# PCB4.net
KiCad netlist of a schematic drawn in EAGLE
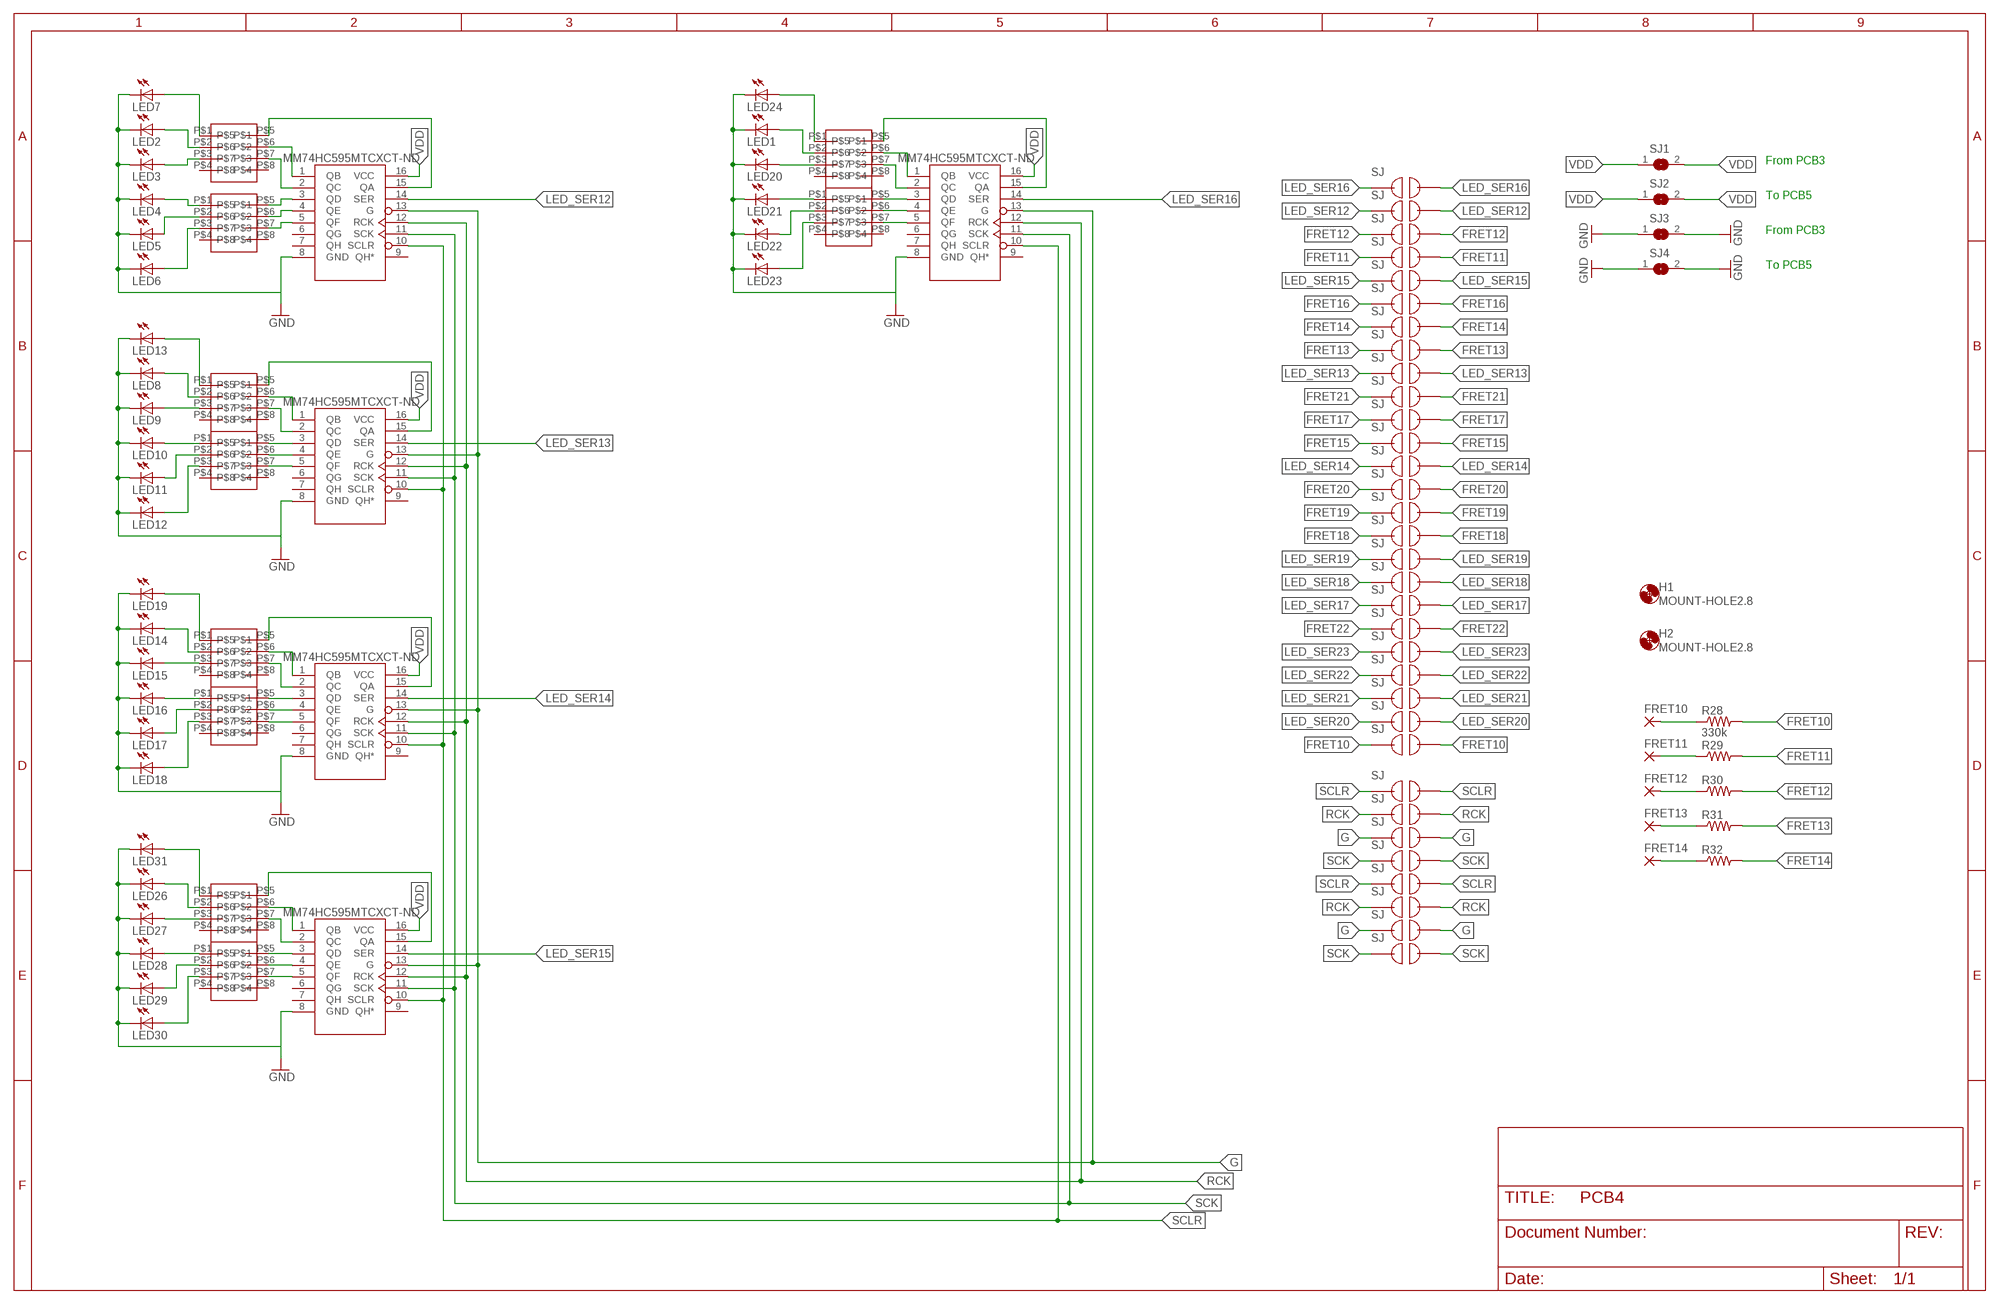
[diagram p0: schematic, sheet 1]

(export (version "E")
  (design (tool "Eeschema 10.0.6"))
  (components
    (comp (ref "FRET10")
      (value "2,54/0,9")
      (footprint "eagle-import:2,54_0,9")
      (libsource (lib "eagle-import") (part "2,54/0,9"))
    )
    (comp (ref "FRET11")
      (value "2,54/0,9")
      (footprint "eagle-import:2,54_0,9")
      (libsource (lib "eagle-import") (part "2,54/0,9"))
    )
    (comp (ref "FRET12")
      (value "2,54/0,9")
      (footprint "eagle-import:2,54_0,9")
      (libsource (lib "eagle-import") (part "2,54/0,9"))
    )
    (comp (ref "FRET13")
      (value "2,54/0,9")
      (footprint "eagle-import:2,54_0,9")
      (libsource (lib "eagle-import") (part "2,54/0,9"))
    )
    (comp (ref "FRET14")
      (value "2,54/0,9")
      (footprint "eagle-import:2,54_0,9")
      (libsource (lib "eagle-import") (part "2,54/0,9"))
    )
    (comp (ref "H1")
      (value "MOUNT-HOLE2.8")
      (footprint "eagle-import:2,8")
      (libsource (lib "eagle-import") (part "MOUNT-HOLE2.8"))
    )
    (comp (ref "H2")
      (value "MOUNT-HOLE2.8")
      (footprint "eagle-import:2,8")
      (libsource (lib "eagle-import") (part "MOUNT-HOLE2.8"))
    )
    (comp (ref "LED1")
      (value "LEDSMT1206")
      (footprint "eagle-import:1206")
      (libsource (lib "eagle-import") (part "LEDSMT1206"))
    )
    (comp (ref "LED2")
      (value "LEDSMT1206")
      (footprint "eagle-import:1206")
      (libsource (lib "eagle-import") (part "LEDSMT1206"))
    )
    (comp (ref "LED3")
      (value "LEDSMT1206")
      (footprint "eagle-import:1206")
      (libsource (lib "eagle-import") (part "LEDSMT1206"))
    )
    (comp (ref "LED4")
      (value "LEDSMT1206")
      (footprint "eagle-import:1206")
      (libsource (lib "eagle-import") (part "LEDSMT1206"))
    )
    (comp (ref "LED5")
      (value "LEDSMT1206")
      (footprint "eagle-import:1206")
      (libsource (lib "eagle-import") (part "LEDSMT1206"))
    )
    (comp (ref "LED6")
      (value "LEDSMT1206")
      (footprint "eagle-import:1206")
      (libsource (lib "eagle-import") (part "LEDSMT1206"))
    )
    (comp (ref "LED7")
      (value "LEDSMT1206")
      (footprint "eagle-import:1206")
      (libsource (lib "eagle-import") (part "LEDSMT1206"))
    )
    (comp (ref "LED8")
      (value "LEDSMT1206")
      (footprint "eagle-import:1206")
      (libsource (lib "eagle-import") (part "LEDSMT1206"))
    )
    (comp (ref "LED9")
      (value "LEDSMT1206")
      (footprint "eagle-import:1206")
      (libsource (lib "eagle-import") (part "LEDSMT1206"))
    )
    (comp (ref "LED10")
      (value "LEDSMT1206")
      (footprint "eagle-import:1206")
      (libsource (lib "eagle-import") (part "LEDSMT1206"))
    )
    (comp (ref "LED11")
      (value "LEDSMT1206")
      (footprint "eagle-import:1206")
      (libsource (lib "eagle-import") (part "LEDSMT1206"))
    )
    (comp (ref "LED12")
      (value "LEDSMT1206")
      (footprint "eagle-import:1206")
      (libsource (lib "eagle-import") (part "LEDSMT1206"))
    )
    (comp (ref "LED13")
      (value "LEDSMT1206")
      (footprint "eagle-import:1206")
      (libsource (lib "eagle-import") (part "LEDSMT1206"))
    )
    (comp (ref "LED14")
      (value "LEDSMT1206")
      (footprint "eagle-import:1206")
      (libsource (lib "eagle-import") (part "LEDSMT1206"))
    )
    (comp (ref "LED15")
      (value "LEDSMT1206")
      (footprint "eagle-import:1206")
      (libsource (lib "eagle-import") (part "LEDSMT1206"))
    )
    (comp (ref "LED16")
      (value "LEDSMT1206")
      (footprint "eagle-import:1206")
      (libsource (lib "eagle-import") (part "LEDSMT1206"))
    )
    (comp (ref "LED17")
      (value "LEDSMT1206")
      (footprint "eagle-import:1206")
      (libsource (lib "eagle-import") (part "LEDSMT1206"))
    )
    (comp (ref "LED18")
      (value "LEDSMT1206")
      (footprint "eagle-import:1206")
      (libsource (lib "eagle-import") (part "LEDSMT1206"))
    )
    (comp (ref "LED19")
      (value "LEDSMT1206")
      (footprint "eagle-import:1206")
      (libsource (lib "eagle-import") (part "LEDSMT1206"))
    )
    (comp (ref "LED20")
      (value "LEDSMT1206")
      (footprint "eagle-import:1206")
      (libsource (lib "eagle-import") (part "LEDSMT1206"))
    )
    (comp (ref "LED21")
      (value "LEDSMT1206")
      (footprint "eagle-import:1206")
      (libsource (lib "eagle-import") (part "LEDSMT1206"))
    )
    (comp (ref "LED22")
      (value "LEDSMT1206")
      (footprint "eagle-import:1206")
      (libsource (lib "eagle-import") (part "LEDSMT1206"))
    )
    (comp (ref "LED23")
      (value "LEDSMT1206")
      (footprint "eagle-import:1206")
      (libsource (lib "eagle-import") (part "LEDSMT1206"))
    )
    (comp (ref "LED24")
      (value "LEDSMT1206")
      (footprint "eagle-import:1206")
      (libsource (lib "eagle-import") (part "LEDSMT1206"))
    )
    (comp (ref "LED26")
      (value "LEDSMT1206")
      (footprint "eagle-import:1206")
      (libsource (lib "eagle-import") (part "LEDSMT1206"))
    )
    (comp (ref "LED27")
      (value "LEDSMT1206")
      (footprint "eagle-import:1206")
      (libsource (lib "eagle-import") (part "LEDSMT1206"))
    )
    (comp (ref "LED28")
      (value "LEDSMT1206")
      (footprint "eagle-import:1206")
      (libsource (lib "eagle-import") (part "LEDSMT1206"))
    )
    (comp (ref "LED29")
      (value "LEDSMT1206")
      (footprint "eagle-import:1206")
      (libsource (lib "eagle-import") (part "LEDSMT1206"))
    )
    (comp (ref "LED30")
      (value "LEDSMT1206")
      (footprint "eagle-import:1206")
      (libsource (lib "eagle-import") (part "LEDSMT1206"))
    )
    (comp (ref "LED31")
      (value "LEDSMT1206")
      (footprint "eagle-import:1206")
      (libsource (lib "eagle-import") (part "LEDSMT1206"))
    )
    (comp (ref "R28")
      (value "330k")
      (footprint "eagle-import:R0805")
      (libsource (lib "eagle-import") (part "R-US_R0805"))
    )
    (comp (ref "R29")
      (value "R-US_R0805")
      (footprint "eagle-import:R0805")
      (libsource (lib "eagle-import") (part "R-US_R0805"))
    )
    (comp (ref "R30")
      (value "R-US_R0805")
      (footprint "eagle-import:R0805")
      (libsource (lib "eagle-import") (part "R-US_R0805"))
    )
    (comp (ref "R31")
      (value "R-US_R0805")
      (footprint "eagle-import:R0805")
      (libsource (lib "eagle-import") (part "R-US_R0805"))
    )
    (comp (ref "R32")
      (value "R-US_R0805")
      (footprint "eagle-import:R0805")
      (libsource (lib "eagle-import") (part "R-US_R0805"))
    )
    (comp (ref "SJ1") (value "SJ") (footprint "eagle-import:SJ") (libsource (lib "eagle-import") (part "SJ")))
    (comp (ref "SJ2") (value "SJ") (footprint "eagle-import:SJ") (libsource (lib "eagle-import") (part "SJ")))
    (comp (ref "SJ3") (value "SJ") (footprint "eagle-import:SJ") (libsource (lib "eagle-import") (part "SJ")))
    (comp (ref "SJ4") (value "SJ") (footprint "eagle-import:SJ") (libsource (lib "eagle-import") (part "SJ")))
    (comp (ref "U$1")
      (value "MM74HC595TSSOP-LD16")
      (footprint "eagle-import:MM74HC595MTCXCT-ND")
      (libsource (lib "eagle-import") (part "MM74HC595TSSOP-LD16"))
    )
    (comp (ref "U$2")
      (value "MM74HC595TSSOP-LD16")
      (footprint "eagle-import:MM74HC595MTCXCT-ND")
      (libsource (lib "eagle-import") (part "MM74HC595TSSOP-LD16"))
    )
    (comp (ref "U$3")
      (value "MM74HC595TSSOP-LD16")
      (footprint "eagle-import:MM74HC595MTCXCT-ND")
      (libsource (lib "eagle-import") (part "MM74HC595TSSOP-LD16"))
    )
    (comp (ref "U$4")
      (value "MM74HC595TSSOP-LD16")
      (footprint "eagle-import:MM74HC595MTCXCT-ND")
      (libsource (lib "eagle-import") (part "MM74HC595TSSOP-LD16"))
    )
    (comp (ref "U$5")
      (value "MM74HC595TSSOP-LD16")
      (footprint "eagle-import:MM74HC595MTCXCT-ND")
      (libsource (lib "eagle-import") (part "MM74HC595TSSOP-LD16"))
    )
    (comp (ref "U$6")
      (value "MNR04MRAPJ680")
      (footprint "eagle-import:MNR04")
      (libsource (lib "eagle-import") (part "MNR04MRAPJ680"))
    )
    (comp (ref "U$7")
      (value "MNR04MRAPJ680")
      (footprint "eagle-import:MNR04")
      (libsource (lib "eagle-import") (part "MNR04MRAPJ680"))
    )
    (comp (ref "U$8")
      (value "MNR04MRAPJ680")
      (footprint "eagle-import:MNR04")
      (libsource (lib "eagle-import") (part "MNR04MRAPJ680"))
    )
    (comp (ref "U$9")
      (value "MNR04MRAPJ680")
      (footprint "eagle-import:MNR04")
      (libsource (lib "eagle-import") (part "MNR04MRAPJ680"))
    )
    (comp (ref "U$10")
      (value "MNR04MRAPJ680")
      (footprint "eagle-import:MNR04")
      (libsource (lib "eagle-import") (part "MNR04MRAPJ680"))
    )
    (comp (ref "U$11")
      (value "MNR04MRAPJ680")
      (footprint "eagle-import:MNR04")
      (libsource (lib "eagle-import") (part "MNR04MRAPJ680"))
    )
    (comp (ref "U$12")
      (value "MNR04MRAPJ680")
      (footprint "eagle-import:MNR04")
      (libsource (lib "eagle-import") (part "MNR04MRAPJ680"))
    )
    (comp (ref "U$13")
      (value "MNR04MRAPJ680")
      (footprint "eagle-import:MNR04")
      (libsource (lib "eagle-import") (part "MNR04MRAPJ680"))
    )
    (comp (ref "U$14")
      (value "MNR04MRAPJ680")
      (footprint "eagle-import:MNR04")
      (libsource (lib "eagle-import") (part "MNR04MRAPJ680"))
    )
    (comp (ref "U$15")
      (value "MNR04MRAPJ680")
      (footprint "eagle-import:MNR04")
      (libsource (lib "eagle-import") (part "MNR04MRAPJ680"))
    )
    (comp (ref "U$19")
      (value "JUMPER")
      (footprint "eagle-import:JUMPER")
      (libsource (lib "eagle-import") (part "JUMPER"))
    )
    (comp (ref "U$42")
      (value "JUMPER")
      (footprint "eagle-import:JUMPER")
      (libsource (lib "eagle-import") (part "JUMPER"))
    )
    (comp (ref "U$45")
      (value "JUMPER")
      (footprint "eagle-import:JUMPER")
      (libsource (lib "eagle-import") (part "JUMPER"))
    )
    (comp (ref "U$46")
      (value "JUMPER")
      (footprint "eagle-import:JUMPER")
      (libsource (lib "eagle-import") (part "JUMPER"))
    )
    (comp (ref "U$47")
      (value "JUMPER")
      (footprint "eagle-import:JUMPER")
      (libsource (lib "eagle-import") (part "JUMPER"))
    )
    (comp (ref "U$48")
      (value "JUMPER")
      (footprint "eagle-import:JUMPER")
      (libsource (lib "eagle-import") (part "JUMPER"))
    )
    (comp (ref "U$49")
      (value "JUMPER")
      (footprint "eagle-import:JUMPER")
      (libsource (lib "eagle-import") (part "JUMPER"))
    )
    (comp (ref "U$50")
      (value "JUMPER")
      (footprint "eagle-import:JUMPER")
      (libsource (lib "eagle-import") (part "JUMPER"))
    )
    (comp (ref "U$51")
      (value "JUMPER")
      (footprint "eagle-import:JUMPER")
      (libsource (lib "eagle-import") (part "JUMPER"))
    )
    (comp (ref "U$52")
      (value "JUMPER")
      (footprint "eagle-import:JUMPER")
      (libsource (lib "eagle-import") (part "JUMPER"))
    )
    (comp (ref "U$53")
      (value "JUMPER")
      (footprint "eagle-import:JUMPER")
      (libsource (lib "eagle-import") (part "JUMPER"))
    )
    (comp (ref "U$54")
      (value "JUMPER")
      (footprint "eagle-import:JUMPER")
      (libsource (lib "eagle-import") (part "JUMPER"))
    )
    (comp (ref "U$55")
      (value "JUMPER")
      (footprint "eagle-import:JUMPER")
      (libsource (lib "eagle-import") (part "JUMPER"))
    )
    (comp (ref "U$56")
      (value "JUMPER")
      (footprint "eagle-import:JUMPER")
      (libsource (lib "eagle-import") (part "JUMPER"))
    )
    (comp (ref "U$57")
      (value "JUMPER")
      (footprint "eagle-import:JUMPER")
      (libsource (lib "eagle-import") (part "JUMPER"))
    )
    (comp (ref "U$58")
      (value "JUMPER")
      (footprint "eagle-import:JUMPER")
      (libsource (lib "eagle-import") (part "JUMPER"))
    )
    (comp (ref "U$59")
      (value "JUMPER")
      (footprint "eagle-import:JUMPER")
      (libsource (lib "eagle-import") (part "JUMPER"))
    )
    (comp (ref "U$60")
      (value "JUMPER")
      (footprint "eagle-import:JUMPER")
      (libsource (lib "eagle-import") (part "JUMPER"))
    )
    (comp (ref "U$61")
      (value "JUMPER")
      (footprint "eagle-import:JUMPER")
      (libsource (lib "eagle-import") (part "JUMPER"))
    )
    (comp (ref "U$62")
      (value "JUMPER")
      (footprint "eagle-import:JUMPER")
      (libsource (lib "eagle-import") (part "JUMPER"))
    )
    (comp (ref "U$63")
      (value "JUMPER")
      (footprint "eagle-import:JUMPER")
      (libsource (lib "eagle-import") (part "JUMPER"))
    )
    (comp (ref "U$64")
      (value "JUMPER")
      (footprint "eagle-import:JUMPER")
      (libsource (lib "eagle-import") (part "JUMPER"))
    )
    (comp (ref "U$65")
      (value "JUMPER")
      (footprint "eagle-import:JUMPER")
      (libsource (lib "eagle-import") (part "JUMPER"))
    )
    (comp (ref "U$66")
      (value "JUMPER")
      (footprint "eagle-import:JUMPER")
      (libsource (lib "eagle-import") (part "JUMPER"))
    )
    (comp (ref "U$67")
      (value "JUMPER")
      (footprint "eagle-import:JUMPER")
      (libsource (lib "eagle-import") (part "JUMPER"))
    )
    (comp (ref "U$68")
      (value "JUMPER")
      (footprint "eagle-import:JUMPER")
      (libsource (lib "eagle-import") (part "JUMPER"))
    )
    (comp (ref "U$69")
      (value "JUMPER")
      (footprint "eagle-import:JUMPER")
      (libsource (lib "eagle-import") (part "JUMPER"))
    )
    (comp (ref "U$79")
      (value "JUMPER")
      (footprint "eagle-import:JUMPER")
      (libsource (lib "eagle-import") (part "JUMPER"))
    )
    (comp (ref "U$80")
      (value "JUMPER")
      (footprint "eagle-import:JUMPER")
      (libsource (lib "eagle-import") (part "JUMPER"))
    )
    (comp (ref "U$81")
      (value "JUMPER")
      (footprint "eagle-import:JUMPER")
      (libsource (lib "eagle-import") (part "JUMPER"))
    )
    (comp (ref "U$82")
      (value "JUMPER")
      (footprint "eagle-import:JUMPER")
      (libsource (lib "eagle-import") (part "JUMPER"))
    )
    (comp (ref "U$83")
      (value "JUMPER")
      (footprint "eagle-import:JUMPER")
      (libsource (lib "eagle-import") (part "JUMPER"))
    )
    (comp (ref "U$84")
      (value "JUMPER")
      (footprint "eagle-import:JUMPER")
      (libsource (lib "eagle-import") (part "JUMPER"))
    )
  )
  (nets
    (net (code "1") (name "FRET10") (class "Default")
      (node (ref "R28") (pin "2") (pinfunction "2_2") (pintype "passive"))
      (node (ref "U$69") (pin "P$1") (pinfunction "P$1_P$1") (pintype "bidirectional"))
      (node (ref "U$69") (pin "P$2") (pinfunction "P$2_P$2") (pintype "bidirectional"))
    )
    (net (code "2") (name "FRET11") (class "Default")
      (node (ref "R29") (pin "2") (pinfunction "2_2") (pintype "passive"))
      (node (ref "U$48") (pin "P$1") (pinfunction "P$1_P$1") (pintype "bidirectional"))
      (node (ref "U$48") (pin "P$2") (pinfunction "P$2_P$2") (pintype "bidirectional"))
    )
    (net (code "3") (name "FRET12") (class "Default")
      (node (ref "R30") (pin "2") (pinfunction "2_2") (pintype "passive"))
      (node (ref "U$47") (pin "P$1") (pinfunction "P$1_P$1") (pintype "bidirectional"))
      (node (ref "U$47") (pin "P$2") (pinfunction "P$2_P$2") (pintype "bidirectional"))
    )
    (net (code "4") (name "FRET13") (class "Default")
      (node (ref "R31") (pin "2") (pinfunction "2_2") (pintype "passive"))
      (node (ref "U$52") (pin "P$1") (pinfunction "P$1_P$1") (pintype "bidirectional"))
      (node (ref "U$52") (pin "P$2") (pinfunction "P$2_P$2") (pintype "bidirectional"))
    )
    (net (code "5") (name "FRET14") (class "Default")
      (node (ref "R32") (pin "2") (pinfunction "2_2") (pintype "passive"))
      (node (ref "U$51") (pin "P$1") (pinfunction "P$1_P$1") (pintype "bidirectional"))
      (node (ref "U$51") (pin "P$2") (pinfunction "P$2_P$2") (pintype "bidirectional"))
    )
    (net (code "6") (name "FRET15") (class "Default")
      (node (ref "U$56") (pin "P$1") (pinfunction "P$1_P$1") (pintype "bidirectional"))
      (node (ref "U$56") (pin "P$2") (pinfunction "P$2_P$2") (pintype "bidirectional"))
    )
    (net (code "7") (name "FRET16") (class "Default")
      (node (ref "U$50") (pin "P$1") (pinfunction "P$1_P$1") (pintype "bidirectional"))
      (node (ref "U$50") (pin "P$2") (pinfunction "P$2_P$2") (pintype "bidirectional"))
    )
    (net (code "8") (name "FRET17") (class "Default")
      (node (ref "U$55") (pin "P$1") (pinfunction "P$1_P$1") (pintype "bidirectional"))
      (node (ref "U$55") (pin "P$2") (pinfunction "P$2_P$2") (pintype "bidirectional"))
    )
    (net (code "9") (name "FRET18") (class "Default")
      (node (ref "U$60") (pin "P$1") (pinfunction "P$1_P$1") (pintype "bidirectional"))
      (node (ref "U$60") (pin "P$2") (pinfunction "P$2_P$2") (pintype "bidirectional"))
    )
    (net (code "10") (name "FRET19") (class "Default")
      (node (ref "U$59") (pin "P$1") (pinfunction "P$1_P$1") (pintype "bidirectional"))
      (node (ref "U$59") (pin "P$2") (pinfunction "P$2_P$2") (pintype "bidirectional"))
    )
    (net (code "11") (name "FRET20") (class "Default")
      (node (ref "U$58") (pin "P$1") (pinfunction "P$1_P$1") (pintype "bidirectional"))
      (node (ref "U$58") (pin "P$2") (pinfunction "P$2_P$2") (pintype "bidirectional"))
    )
    (net (code "12") (name "FRET21") (class "Default")
      (node (ref "U$54") (pin "P$1") (pinfunction "P$1_P$1") (pintype "bidirectional"))
      (node (ref "U$54") (pin "P$2") (pinfunction "P$2_P$2") (pintype "bidirectional"))
    )
    (net (code "13") (name "FRET22") (class "Default")
      (node (ref "U$64") (pin "P$1") (pinfunction "P$1_P$1") (pintype "bidirectional"))
      (node (ref "U$64") (pin "P$2") (pinfunction "P$2_P$2") (pintype "bidirectional"))
    )
    (net (code "14") (name "G") (class "Default")
      (node (ref "U$1") (pin "13") (pinfunction "G_13") (pintype "bidirectional"))
      (node (ref "U$2") (pin "13") (pinfunction "G_13") (pintype "bidirectional"))
      (node (ref "U$3") (pin "13") (pinfunction "G_13") (pintype "bidirectional"))
      (node (ref "U$4") (pin "13") (pinfunction "G_13") (pintype "bidirectional"))
      (node (ref "U$5") (pin "13") (pinfunction "G_13") (pintype "bidirectional"))
      (node (ref "U$80") (pin "P$1") (pinfunction "P$1_P$1") (pintype "bidirectional"))
      (node (ref "U$80") (pin "P$2") (pinfunction "P$2_P$2") (pintype "bidirectional"))
      (node (ref "U$84") (pin "P$1") (pinfunction "P$1_P$1") (pintype "bidirectional"))
      (node (ref "U$84") (pin "P$2") (pinfunction "P$2_P$2") (pintype "bidirectional"))
    )
    (net (code "15") (name "GND") (class "Default")
      (node (ref "LED1") (pin "C") (pinfunction "C_C") (pintype "passive"))
      (node (ref "LED10") (pin "C") (pinfunction "C_C") (pintype "passive"))
      (node (ref "LED11") (pin "C") (pinfunction "C_C") (pintype "passive"))
      (node (ref "LED12") (pin "C") (pinfunction "C_C") (pintype "passive"))
      (node (ref "LED13") (pin "C") (pinfunction "C_C") (pintype "passive"))
      (node (ref "LED14") (pin "C") (pinfunction "C_C") (pintype "passive"))
      (node (ref "LED15") (pin "C") (pinfunction "C_C") (pintype "passive"))
      (node (ref "LED16") (pin "C") (pinfunction "C_C") (pintype "passive"))
      (node (ref "LED17") (pin "C") (pinfunction "C_C") (pintype "passive"))
      (node (ref "LED18") (pin "C") (pinfunction "C_C") (pintype "passive"))
      (node (ref "LED19") (pin "C") (pinfunction "C_C") (pintype "passive"))
      (node (ref "LED2") (pin "C") (pinfunction "C_C") (pintype "passive"))
      (node (ref "LED20") (pin "C") (pinfunction "C_C") (pintype "passive"))
      (node (ref "LED21") (pin "C") (pinfunction "C_C") (pintype "passive"))
      (node (ref "LED22") (pin "C") (pinfunction "C_C") (pintype "passive"))
      (node (ref "LED23") (pin "C") (pinfunction "C_C") (pintype "passive"))
      (node (ref "LED24") (pin "C") (pinfunction "C_C") (pintype "passive"))
      (node (ref "LED26") (pin "C") (pinfunction "C_C") (pintype "passive"))
      (node (ref "LED27") (pin "C") (pinfunction "C_C") (pintype "passive"))
      (node (ref "LED28") (pin "C") (pinfunction "C_C") (pintype "passive"))
      (node (ref "LED29") (pin "C") (pinfunction "C_C") (pintype "passive"))
      (node (ref "LED3") (pin "C") (pinfunction "C_C") (pintype "passive"))
      (node (ref "LED30") (pin "C") (pinfunction "C_C") (pintype "passive"))
      (node (ref "LED31") (pin "C") (pinfunction "C_C") (pintype "passive"))
      (node (ref "LED4") (pin "C") (pinfunction "C_C") (pintype "passive"))
      (node (ref "LED5") (pin "C") (pinfunction "C_C") (pintype "passive"))
      (node (ref "LED6") (pin "C") (pinfunction "C_C") (pintype "passive"))
      (node (ref "LED7") (pin "C") (pinfunction "C_C") (pintype "passive"))
      (node (ref "LED8") (pin "C") (pinfunction "C_C") (pintype "passive"))
      (node (ref "LED9") (pin "C") (pinfunction "C_C") (pintype "passive"))
      (node (ref "SJ3") (pin "1") (pinfunction "1_1") (pintype "passive"))
      (node (ref "SJ3") (pin "2") (pinfunction "2_2") (pintype "passive"))
      (node (ref "SJ4") (pin "1") (pinfunction "1_1") (pintype "passive"))
      (node (ref "SJ4") (pin "2") (pinfunction "2_2") (pintype "passive"))
      (node (ref "U$1") (pin "8") (pinfunction "GND_8") (pintype "bidirectional"))
      (node (ref "U$2") (pin "8") (pinfunction "GND_8") (pintype "bidirectional"))
      (node (ref "U$3") (pin "8") (pinfunction "GND_8") (pintype "bidirectional"))
      (node (ref "U$4") (pin "8") (pinfunction "GND_8") (pintype "bidirectional"))
      (node (ref "U$5") (pin "8") (pinfunction "GND_8") (pintype "bidirectional"))
    )
    (net (code "16") (name "LED_SER12") (class "Default")
      (node (ref "U$4") (pin "14") (pinfunction "SER_14") (pintype "bidirectional"))
      (node (ref "U$46") (pin "P$1") (pinfunction "P$1_P$1") (pintype "bidirectional"))
      (node (ref "U$46") (pin "P$2") (pinfunction "P$2_P$2") (pintype "bidirectional"))
    )
    (net (code "17") (name "LED_SER13") (class "Default")
      (node (ref "U$1") (pin "14") (pinfunction "SER_14") (pintype "bidirectional"))
      (node (ref "U$53") (pin "P$1") (pinfunction "P$1_P$1") (pintype "bidirectional"))
      (node (ref "U$53") (pin "P$2") (pinfunction "P$2_P$2") (pintype "bidirectional"))
    )
    (net (code "18") (name "LED_SER14") (class "Default")
      (node (ref "U$3") (pin "14") (pinfunction "SER_14") (pintype "bidirectional"))
      (node (ref "U$57") (pin "P$1") (pinfunction "P$1_P$1") (pintype "bidirectional"))
      (node (ref "U$57") (pin "P$2") (pinfunction "P$2_P$2") (pintype "bidirectional"))
    )
    (net (code "19") (name "LED_SER15") (class "Default")
      (node (ref "U$49") (pin "P$1") (pinfunction "P$1_P$1") (pintype "bidirectional"))
      (node (ref "U$49") (pin "P$2") (pinfunction "P$2_P$2") (pintype "bidirectional"))
      (node (ref "U$5") (pin "14") (pinfunction "SER_14") (pintype "bidirectional"))
    )
    (net (code "20") (name "LED_SER16") (class "Default")
      (node (ref "U$2") (pin "14") (pinfunction "SER_14") (pintype "bidirectional"))
      (node (ref "U$45") (pin "P$1") (pinfunction "P$1_P$1") (pintype "bidirectional"))
      (node (ref "U$45") (pin "P$2") (pinfunction "P$2_P$2") (pintype "bidirectional"))
    )
    (net (code "21") (name "LED_SER17") (class "Default")
      (node (ref "U$63") (pin "P$1") (pinfunction "P$1_P$1") (pintype "bidirectional"))
      (node (ref "U$63") (pin "P$2") (pinfunction "P$2_P$2") (pintype "bidirectional"))
    )
    (net (code "22") (name "LED_SER18") (class "Default")
      (node (ref "U$62") (pin "P$1") (pinfunction "P$1_P$1") (pintype "bidirectional"))
      (node (ref "U$62") (pin "P$2") (pinfunction "P$2_P$2") (pintype "bidirectional"))
    )
    (net (code "23") (name "LED_SER19") (class "Default")
      (node (ref "U$61") (pin "P$1") (pinfunction "P$1_P$1") (pintype "bidirectional"))
      (node (ref "U$61") (pin "P$2") (pinfunction "P$2_P$2") (pintype "bidirectional"))
    )
    (net (code "24") (name "LED_SER20") (class "Default")
      (node (ref "U$68") (pin "P$1") (pinfunction "P$1_P$1") (pintype "bidirectional"))
      (node (ref "U$68") (pin "P$2") (pinfunction "P$2_P$2") (pintype "bidirectional"))
    )
    (net (code "25") (name "LED_SER21") (class "Default")
      (node (ref "U$67") (pin "P$1") (pinfunction "P$1_P$1") (pintype "bidirectional"))
      (node (ref "U$67") (pin "P$2") (pinfunction "P$2_P$2") (pintype "bidirectional"))
    )
    (net (code "26") (name "LED_SER22") (class "Default")
      (node (ref "U$66") (pin "P$1") (pinfunction "P$1_P$1") (pintype "bidirectional"))
      (node (ref "U$66") (pin "P$2") (pinfunction "P$2_P$2") (pintype "bidirectional"))
    )
    (net (code "27") (name "LED_SER23") (class "Default")
      (node (ref "U$65") (pin "P$1") (pinfunction "P$1_P$1") (pintype "bidirectional"))
      (node (ref "U$65") (pin "P$2") (pinfunction "P$2_P$2") (pintype "bidirectional"))
    )
    (net (code "28") (name "Net-(FRET10-P)") (class "Default")
      (node (ref "FRET10") (pin "1") (pinfunction "P_1") (pintype "passive"))
      (node (ref "R28") (pin "1") (pinfunction "1_1") (pintype "passive"))
    )
    (net (code "29") (name "Net-(FRET11-P)") (class "Default")
      (node (ref "FRET11") (pin "1") (pinfunction "P_1") (pintype "passive"))
      (node (ref "R29") (pin "1") (pinfunction "1_1") (pintype "passive"))
    )
    (net (code "30") (name "Net-(FRET12-P)") (class "Default")
      (node (ref "FRET12") (pin "1") (pinfunction "P_1") (pintype "passive"))
      (node (ref "R30") (pin "1") (pinfunction "1_1") (pintype "passive"))
    )
    (net (code "31") (name "Net-(FRET13-P)") (class "Default")
      (node (ref "FRET13") (pin "1") (pinfunction "P_1") (pintype "passive"))
      (node (ref "R31") (pin "1") (pinfunction "1_1") (pintype "passive"))
    )
    (net (code "32") (name "Net-(FRET14-P)") (class "Default")
      (node (ref "FRET14") (pin "1") (pinfunction "P_1") (pintype "passive"))
      (node (ref "R32") (pin "1") (pinfunction "1_1") (pintype "passive"))
    )
    (net (code "33") (name "Net-(LED1-PadA)") (class "Default")
      (node (ref "LED1") (pin "A") (pinfunction "A_A") (pintype "passive"))
      (node (ref "U$14") (pin "P$2") (pinfunction "P$2_P$2") (pintype "bidirectional"))
    )
    (net (code "34") (name "Net-(LED2-PadA)") (class "Default")
      (node (ref "LED2") (pin "A") (pinfunction "A_A") (pintype "passive"))
      (node (ref "U$6") (pin "P$2") (pinfunction "P$2_P$2") (pintype "bidirectional"))
    )
    (net (code "35") (name "Net-(LED3-PadA)") (class "Default")
      (node (ref "LED3") (pin "A") (pinfunction "A_A") (pintype "passive"))
      (node (ref "U$6") (pin "P$3") (pinfunction "P$3_P$3") (pintype "bidirectional"))
    )
    (net (code "36") (name "Net-(LED4-PadA)") (class "Default")
      (node (ref "LED4") (pin "A") (pinfunction "A_A") (pintype "passive"))
      (node (ref "U$7") (pin "P$1") (pinfunction "P$1_P$1") (pintype "bidirectional"))
    )
    (net (code "37") (name "Net-(LED5-PadA)") (class "Default")
      (node (ref "LED5") (pin "A") (pinfunction "A_A") (pintype "passive"))
      (node (ref "U$7") (pin "P$2") (pinfunction "P$2_P$2") (pintype "bidirectional"))
    )
    (net (code "38") (name "Net-(LED6-PadA)") (class "Default")
      (node (ref "LED6") (pin "A") (pinfunction "A_A") (pintype "passive"))
      (node (ref "U$7") (pin "P$3") (pinfunction "P$3_P$3") (pintype "bidirectional"))
    )
    (net (code "39") (name "Net-(LED7-PadA)") (class "Default")
      (node (ref "LED7") (pin "A") (pinfunction "A_A") (pintype "passive"))
      (node (ref "U$6") (pin "P$1") (pinfunction "P$1_P$1") (pintype "bidirectional"))
    )
    (net (code "40") (name "Net-(LED8-PadA)") (class "Default")
      (node (ref "LED8") (pin "A") (pinfunction "A_A") (pintype "passive"))
      (node (ref "U$8") (pin "P$2") (pinfunction "P$2_P$2") (pintype "bidirectional"))
    )
    (net (code "41") (name "Net-(LED9-PadA)") (class "Default")
      (node (ref "LED9") (pin "A") (pinfunction "A_A") (pintype "passive"))
      (node (ref "U$8") (pin "P$3") (pinfunction "P$3_P$3") (pintype "bidirectional"))
    )
    (net (code "42") (name "Net-(LED10-PadA)") (class "Default")
      (node (ref "LED10") (pin "A") (pinfunction "A_A") (pintype "passive"))
      (node (ref "U$9") (pin "P$1") (pinfunction "P$1_P$1") (pintype "bidirectional"))
    )
    (net (code "43") (name "Net-(LED11-PadA)") (class "Default")
      (node (ref "LED11") (pin "A") (pinfunction "A_A") (pintype "passive"))
      (node (ref "U$9") (pin "P$2") (pinfunction "P$2_P$2") (pintype "bidirectional"))
    )
    (net (code "44") (name "Net-(LED12-PadA)") (class "Default")
      (node (ref "LED12") (pin "A") (pinfunction "A_A") (pintype "passive"))
      (node (ref "U$9") (pin "P$3") (pinfunction "P$3_P$3") (pintype "bidirectional"))
    )
    (net (code "45") (name "Net-(LED13-PadA)") (class "Default")
      (node (ref "LED13") (pin "A") (pinfunction "A_A") (pintype "passive"))
      (node (ref "U$8") (pin "P$1") (pinfunction "P$1_P$1") (pintype "bidirectional"))
    )
    (net (code "46") (name "Net-(LED14-PadA)") (class "Default")
      (node (ref "LED14") (pin "A") (pinfunction "A_A") (pintype "passive"))
      (node (ref "U$10") (pin "P$2") (pinfunction "P$2_P$2") (pintype "bidirectional"))
    )
    (net (code "47") (name "Net-(LED15-PadA)") (class "Default")
      (node (ref "LED15") (pin "A") (pinfunction "A_A") (pintype "passive"))
      (node (ref "U$10") (pin "P$3") (pinfunction "P$3_P$3") (pintype "bidirectional"))
    )
    (net (code "48") (name "Net-(LED16-PadA)") (class "Default")
      (node (ref "LED16") (pin "A") (pinfunction "A_A") (pintype "passive"))
      (node (ref "U$11") (pin "P$1") (pinfunction "P$1_P$1") (pintype "bidirectional"))
    )
    (net (code "49") (name "Net-(LED17-PadA)") (class "Default")
      (node (ref "LED17") (pin "A") (pinfunction "A_A") (pintype "passive"))
      (node (ref "U$11") (pin "P$2") (pinfunction "P$2_P$2") (pintype "bidirectional"))
    )
    (net (code "50") (name "Net-(LED18-PadA)") (class "Default")
      (node (ref "LED18") (pin "A") (pinfunction "A_A") (pintype "passive"))
      (node (ref "U$11") (pin "P$3") (pinfunction "P$3_P$3") (pintype "bidirectional"))
    )
    (net (code "51") (name "Net-(LED19-PadA)") (class "Default")
      (node (ref "LED19") (pin "A") (pinfunction "A_A") (pintype "passive"))
      (node (ref "U$10") (pin "P$1") (pinfunction "P$1_P$1") (pintype "bidirectional"))
    )
    (net (code "52") (name "Net-(LED20-PadA)") (class "Default")
      (node (ref "LED20") (pin "A") (pinfunction "A_A") (pintype "passive"))
      (node (ref "U$14") (pin "P$3") (pinfunction "P$3_P$3") (pintype "bidirectional"))
    )
    (net (code "53") (name "Net-(LED21-PadA)") (class "Default")
      (node (ref "LED21") (pin "A") (pinfunction "A_A") (pintype "passive"))
      (node (ref "U$15") (pin "P$1") (pinfunction "P$1_P$1") (pintype "bidirectional"))
    )
    (net (code "54") (name "Net-(LED22-PadA)") (class "Default")
      (node (ref "LED22") (pin "A") (pinfunction "A_A") (pintype "passive"))
      (node (ref "U$15") (pin "P$2") (pinfunction "P$2_P$2") (pintype "bidirectional"))
    )
    (net (code "55") (name "Net-(LED23-PadA)") (class "Default")
      (node (ref "LED23") (pin "A") (pinfunction "A_A") (pintype "passive"))
      (node (ref "U$15") (pin "P$3") (pinfunction "P$3_P$3") (pintype "bidirectional"))
    )
    (net (code "56") (name "Net-(LED24-PadA)") (class "Default")
      (node (ref "LED24") (pin "A") (pinfunction "A_A") (pintype "passive"))
      (node (ref "U$14") (pin "P$1") (pinfunction "P$1_P$1") (pintype "bidirectional"))
    )
    (net (code "57") (name "Net-(LED26-PadA)") (class "Default")
      (node (ref "LED26") (pin "A") (pinfunction "A_A") (pintype "passive"))
      (node (ref "U$12") (pin "P$2") (pinfunction "P$2_P$2") (pintype "bidirectional"))
    )
    (net (code "58") (name "Net-(LED27-PadA)") (class "Default")
      (node (ref "LED27") (pin "A") (pinfunction "A_A") (pintype "passive"))
      (node (ref "U$12") (pin "P$3") (pinfunction "P$3_P$3") (pintype "bidirectional"))
    )
    (net (code "59") (name "Net-(LED28-PadA)") (class "Default")
      (node (ref "LED28") (pin "A") (pinfunction "A_A") (pintype "passive"))
      (node (ref "U$13") (pin "P$1") (pinfunction "P$1_P$1") (pintype "bidirectional"))
    )
    (net (code "60") (name "Net-(LED29-PadA)") (class "Default")
      (node (ref "LED29") (pin "A") (pinfunction "A_A") (pintype "passive"))
      (node (ref "U$13") (pin "P$2") (pinfunction "P$2_P$2") (pintype "bidirectional"))
    )
    (net (code "61") (name "Net-(LED30-PadA)") (class "Default")
      (node (ref "LED30") (pin "A") (pinfunction "A_A") (pintype "passive"))
      (node (ref "U$13") (pin "P$3") (pinfunction "P$3_P$3") (pintype "bidirectional"))
    )
    (net (code "62") (name "Net-(LED31-PadA)") (class "Default")
      (node (ref "LED31") (pin "A") (pinfunction "A_A") (pintype "passive"))
      (node (ref "U$12") (pin "P$1") (pinfunction "P$1_P$1") (pintype "bidirectional"))
    )
    (net (code "63") (name "Net-(U$1-QA)") (class "Default")
      (node (ref "U$1") (pin "15") (pinfunction "QA_15") (pintype "bidirectional"))
      (node (ref "U$8") (pin "P$5") (pinfunction "P$5_P$5") (pintype "bidirectional"))
    )
    (net (code "64") (name "Net-(U$1-QB)") (class "Default")
      (node (ref "U$1") (pin "1") (pinfunction "QB_1") (pintype "bidirectional"))
      (node (ref "U$8") (pin "P$6") (pinfunction "P$6_P$6") (pintype "bidirectional"))
    )
    (net (code "65") (name "Net-(U$1-QC)") (class "Default")
      (node (ref "U$1") (pin "2") (pinfunction "QC_2") (pintype "bidirectional"))
      (node (ref "U$8") (pin "P$7") (pinfunction "P$7_P$7") (pintype "bidirectional"))
    )
    (net (code "66") (name "Net-(U$1-QD)") (class "Default")
      (node (ref "U$1") (pin "3") (pinfunction "QD_3") (pintype "bidirectional"))
      (node (ref "U$9") (pin "P$5") (pinfunction "P$5_P$5") (pintype "bidirectional"))
    )
    (net (code "67") (name "Net-(U$1-QE)") (class "Default")
      (node (ref "U$1") (pin "4") (pinfunction "QE_4") (pintype "bidirectional"))
      (node (ref "U$9") (pin "P$6") (pinfunction "P$6_P$6") (pintype "bidirectional"))
    )
    (net (code "68") (name "Net-(U$1-QF)") (class "Default")
      (node (ref "U$1") (pin "5") (pinfunction "QF_5") (pintype "bidirectional"))
      (node (ref "U$9") (pin "P$7") (pinfunction "P$7_P$7") (pintype "bidirectional"))
    )
    (net (code "69") (name "Net-(U$2-QA)") (class "Default")
      (node (ref "U$14") (pin "P$5") (pinfunction "P$5_P$5") (pintype "bidirectional"))
      (node (ref "U$2") (pin "15") (pinfunction "QA_15") (pintype "bidirectional"))
    )
    (net (code "70") (name "Net-(U$2-QB)") (class "Default")
      (node (ref "U$14") (pin "P$6") (pinfunction "P$6_P$6") (pintype "bidirectional"))
      (node (ref "U$2") (pin "1") (pinfunction "QB_1") (pintype "bidirectional"))
    )
    (net (code "71") (name "Net-(U$2-QC)") (class "Default")
      (node (ref "U$14") (pin "P$7") (pinfunction "P$7_P$7") (pintype "bidirectional"))
      (node (ref "U$2") (pin "2") (pinfunction "QC_2") (pintype "bidirectional"))
    )
    (net (code "72") (name "Net-(U$2-QD)") (class "Default")
      (node (ref "U$15") (pin "P$5") (pinfunction "P$5_P$5") (pintype "bidirectional"))
      (node (ref "U$2") (pin "3") (pinfunction "QD_3") (pintype "bidirectional"))
    )
    (net (code "73") (name "Net-(U$2-QE)") (class "Default")
      (node (ref "U$15") (pin "P$6") (pinfunction "P$6_P$6") (pintype "bidirectional"))
      (node (ref "U$2") (pin "4") (pinfunction "QE_4") (pintype "bidirectional"))
    )
    (net (code "74") (name "Net-(U$2-QF)") (class "Default")
      (node (ref "U$15") (pin "P$7") (pinfunction "P$7_P$7") (pintype "bidirectional"))
      (node (ref "U$2") (pin "5") (pinfunction "QF_5") (pintype "bidirectional"))
    )
    (net (code "75") (name "Net-(U$3-QA)") (class "Default")
      (node (ref "U$10") (pin "P$5") (pinfunction "P$5_P$5") (pintype "bidirectional"))
      (node (ref "U$3") (pin "15") (pinfunction "QA_15") (pintype "bidirectional"))
    )
    (net (code "76") (name "Net-(U$3-QB)") (class "Default")
      (node (ref "U$10") (pin "P$6") (pinfunction "P$6_P$6") (pintype "bidirectional"))
      (node (ref "U$3") (pin "1") (pinfunction "QB_1") (pintype "bidirectional"))
    )
    (net (code "77") (name "Net-(U$3-QC)") (class "Default")
      (node (ref "U$10") (pin "P$7") (pinfunction "P$7_P$7") (pintype "bidirectional"))
      (node (ref "U$3") (pin "2") (pinfunction "QC_2") (pintype "bidirectional"))
    )
    (net (code "78") (name "Net-(U$3-QD)") (class "Default")
      (node (ref "U$11") (pin "P$5") (pinfunction "P$5_P$5") (pintype "bidirectional"))
      (node (ref "U$3") (pin "3") (pinfunction "QD_3") (pintype "bidirectional"))
    )
    (net (code "79") (name "Net-(U$3-QE)") (class "Default")
      (node (ref "U$11") (pin "P$6") (pinfunction "P$6_P$6") (pintype "bidirectional"))
      (node (ref "U$3") (pin "4") (pinfunction "QE_4") (pintype "bidirectional"))
    )
    (net (code "80") (name "Net-(U$3-QF)") (class "Default")
      (node (ref "U$11") (pin "P$7") (pinfunction "P$7_P$7") (pintype "bidirectional"))
      (node (ref "U$3") (pin "5") (pinfunction "QF_5") (pintype "bidirectional"))
    )
    (net (code "81") (name "Net-(U$4-QA)") (class "Default")
      (node (ref "U$4") (pin "15") (pinfunction "QA_15") (pintype "bidirectional"))
      (node (ref "U$6") (pin "P$5") (pinfunction "P$5_P$5") (pintype "bidirectional"))
    )
    (net (code "82") (name "Net-(U$4-QB)") (class "Default")
      (node (ref "U$4") (pin "1") (pinfunction "QB_1") (pintype "bidirectional"))
      (node (ref "U$6") (pin "P$6") (pinfunction "P$6_P$6") (pintype "bidirectional"))
    )
    (net (code "83") (name "Net-(U$4-QC)") (class "Default")
      (node (ref "U$4") (pin "2") (pinfunction "QC_2") (pintype "bidirectional"))
      (node (ref "U$6") (pin "P$7") (pinfunction "P$7_P$7") (pintype "bidirectional"))
    )
    (net (code "84") (name "Net-(U$4-QD)") (class "Default")
      (node (ref "U$4") (pin "3") (pinfunction "QD_3") (pintype "bidirectional"))
      (node (ref "U$7") (pin "P$5") (pinfunction "P$5_P$5") (pintype "bidirectional"))
    )
    (net (code "85") (name "Net-(U$4-QE)") (class "Default")
      (node (ref "U$4") (pin "4") (pinfunction "QE_4") (pintype "bidirectional"))
      (node (ref "U$7") (pin "P$6") (pinfunction "P$6_P$6") (pintype "bidirectional"))
    )
    (net (code "86") (name "Net-(U$4-QF)") (class "Default")
      (node (ref "U$4") (pin "5") (pinfunction "QF_5") (pintype "bidirectional"))
      (node (ref "U$7") (pin "P$7") (pinfunction "P$7_P$7") (pintype "bidirectional"))
    )
    (net (code "87") (name "Net-(U$5-QA)") (class "Default")
      (node (ref "U$12") (pin "P$5") (pinfunction "P$5_P$5") (pintype "bidirectional"))
      (node (ref "U$5") (pin "15") (pinfunction "QA_15") (pintype "bidirectional"))
    )
    (net (code "88") (name "Net-(U$5-QB)") (class "Default")
      (node (ref "U$12") (pin "P$6") (pinfunction "P$6_P$6") (pintype "bidirectional"))
      (node (ref "U$5") (pin "1") (pinfunction "QB_1") (pintype "bidirectional"))
    )
    (net (code "89") (name "Net-(U$5-QC)") (class "Default")
      (node (ref "U$12") (pin "P$7") (pinfunction "P$7_P$7") (pintype "bidirectional"))
      (node (ref "U$5") (pin "2") (pinfunction "QC_2") (pintype "bidirectional"))
    )
    (net (code "90") (name "Net-(U$5-QD)") (class "Default")
      (node (ref "U$13") (pin "P$5") (pinfunction "P$5_P$5") (pintype "bidirectional"))
      (node (ref "U$5") (pin "3") (pinfunction "QD_3") (pintype "bidirectional"))
    )
    (net (code "91") (name "Net-(U$5-QE)") (class "Default")
      (node (ref "U$13") (pin "P$6") (pinfunction "P$6_P$6") (pintype "bidirectional"))
      (node (ref "U$5") (pin "4") (pinfunction "QE_4") (pintype "bidirectional"))
    )
    (net (code "92") (name "Net-(U$5-QF)") (class "Default")
      (node (ref "U$13") (pin "P$7") (pinfunction "P$7_P$7") (pintype "bidirectional"))
      (node (ref "U$5") (pin "5") (pinfunction "QF_5") (pintype "bidirectional"))
    )
    (net (code "93") (name "RCK") (class "Default")
      (node (ref "U$1") (pin "12") (pinfunction "RCK_12") (pintype "bidirectional"))
      (node (ref "U$2") (pin "12") (pinfunction "RCK_12") (pintype "bidirectional"))
      (node (ref "U$3") (pin "12") (pinfunction "RCK_12") (pintype "bidirectional"))
      (node (ref "U$4") (pin "12") (pinfunction "RCK_12") (pintype "bidirectional"))
      (node (ref "U$5") (pin "12") (pinfunction "RCK_12") (pintype "bidirectional"))
      (node (ref "U$79") (pin "P$1") (pinfunction "P$1_P$1") (pintype "bidirectional"))
      (node (ref "U$79") (pin "P$2") (pinfunction "P$2_P$2") (pintype "bidirectional"))
      (node (ref "U$83") (pin "P$1") (pinfunction "P$1_P$1") (pintype "bidirectional"))
      (node (ref "U$83") (pin "P$2") (pinfunction "P$2_P$2") (pintype "bidirectional"))
    )
    (net (code "94") (name "SCK") (class "Default")
      (node (ref "U$1") (pin "11") (pinfunction "SCK_11") (pintype "bidirectional"))
      (node (ref "U$2") (pin "11") (pinfunction "SCK_11") (pintype "bidirectional"))
      (node (ref "U$3") (pin "11") (pinfunction "SCK_11") (pintype "bidirectional"))
      (node (ref "U$4") (pin "11") (pinfunction "SCK_11") (pintype "bidirectional"))
      (node (ref "U$42") (pin "P$1") (pinfunction "P$1_P$1") (pintype "bidirectional"))
      (node (ref "U$42") (pin "P$2") (pinfunction "P$2_P$2") (pintype "bidirectional"))
      (node (ref "U$5") (pin "11") (pinfunction "SCK_11") (pintype "bidirectional"))
      (node (ref "U$81") (pin "P$1") (pinfunction "P$1_P$1") (pintype "bidirectional"))
      (node (ref "U$81") (pin "P$2") (pinfunction "P$2_P$2") (pintype "bidirectional"))
    )
    (net (code "95") (name "SCLR") (class "Default")
      (node (ref "U$1") (pin "10") (pinfunction "SCLR_10") (pintype "bidirectional"))
      (node (ref "U$19") (pin "P$1") (pinfunction "P$1_P$1") (pintype "bidirectional"))
      (node (ref "U$19") (pin "P$2") (pinfunction "P$2_P$2") (pintype "bidirectional"))
      (node (ref "U$2") (pin "10") (pinfunction "SCLR_10") (pintype "bidirectional"))
      (node (ref "U$3") (pin "10") (pinfunction "SCLR_10") (pintype "bidirectional"))
      (node (ref "U$4") (pin "10") (pinfunction "SCLR_10") (pintype "bidirectional"))
      (node (ref "U$5") (pin "10") (pinfunction "SCLR_10") (pintype "bidirectional"))
      (node (ref "U$82") (pin "P$1") (pinfunction "P$1_P$1") (pintype "bidirectional"))
      (node (ref "U$82") (pin "P$2") (pinfunction "P$2_P$2") (pintype "bidirectional"))
    )
    (net (code "96") (name "VDD") (class "Default")
      (node (ref "SJ1") (pin "1") (pinfunction "1_1") (pintype "passive"))
      (node (ref "SJ1") (pin "2") (pinfunction "2_2") (pintype "passive"))
      (node (ref "SJ2") (pin "1") (pinfunction "1_1") (pintype "passive"))
      (node (ref "SJ2") (pin "2") (pinfunction "2_2") (pintype "passive"))
      (node (ref "U$1") (pin "16") (pinfunction "VCC_16") (pintype "bidirectional"))
      (node (ref "U$2") (pin "16") (pinfunction "VCC_16") (pintype "bidirectional"))
      (node (ref "U$3") (pin "16") (pinfunction "VCC_16") (pintype "bidirectional"))
      (node (ref "U$4") (pin "16") (pinfunction "VCC_16") (pintype "bidirectional"))
      (node (ref "U$5") (pin "16") (pinfunction "VCC_16") (pintype "bidirectional"))
    )
    (net (code "97") (name "unconnected-(U$1-QG-Pad6)") (class "Default")
      (node (ref "U$1") (pin "6") (pinfunction "QG_6") (pintype "bidirectional"))
    )
    (net (code "98") (name "unconnected-(U$1-QH*-Pad9)") (class "Default")
      (node (ref "U$1") (pin "9") (pinfunction "QH*_9") (pintype "bidirectional"))
    )
    (net (code "99") (name "unconnected-(U$1-QH-Pad7)") (class "Default")
      (node (ref "U$1") (pin "7") (pinfunction "QH_7") (pintype "bidirectional"))
    )
    (net (code "100") (name "unconnected-(U$2-QG-Pad6)") (class "Default")
      (node (ref "U$2") (pin "6") (pinfunction "QG_6") (pintype "bidirectional"))
    )
    (net (code "101") (name "unconnected-(U$2-QH*-Pad9)") (class "Default")
      (node (ref "U$2") (pin "9") (pinfunction "QH*_9") (pintype "bidirectional"))
    )
    (net (code "102") (name "unconnected-(U$2-QH-Pad7)") (class "Default")
      (node (ref "U$2") (pin "7") (pinfunction "QH_7") (pintype "bidirectional"))
    )
    (net (code "103") (name "unconnected-(U$3-QG-Pad6)") (class "Default")
      (node (ref "U$3") (pin "6") (pinfunction "QG_6") (pintype "bidirectional"))
    )
    (net (code "104") (name "unconnected-(U$3-QH*-Pad9)") (class "Default")
      (node (ref "U$3") (pin "9") (pinfunction "QH*_9") (pintype "bidirectional"))
    )
    (net (code "105") (name "unconnected-(U$3-QH-Pad7)") (class "Default")
      (node (ref "U$3") (pin "7") (pinfunction "QH_7") (pintype "bidirectional"))
    )
    (net (code "106") (name "unconnected-(U$4-QG-Pad6)") (class "Default")
      (node (ref "U$4") (pin "6") (pinfunction "QG_6") (pintype "bidirectional"))
    )
    (net (code "107") (name "unconnected-(U$4-QH*-Pad9)") (class "Default")
      (node (ref "U$4") (pin "9") (pinfunction "QH*_9") (pintype "bidirectional"))
    )
    (net (code "108") (name "unconnected-(U$4-QH-Pad7)") (class "Default")
      (node (ref "U$4") (pin "7") (pinfunction "QH_7") (pintype "bidirectional"))
    )
    (net (code "109") (name "unconnected-(U$5-QG-Pad6)") (class "Default")
      (node (ref "U$5") (pin "6") (pinfunction "QG_6") (pintype "bidirectional"))
    )
    (net (code "110") (name "unconnected-(U$5-QH*-Pad9)") (class "Default")
      (node (ref "U$5") (pin "9") (pinfunction "QH*_9") (pintype "bidirectional"))
    )
    (net (code "111") (name "unconnected-(U$5-QH-Pad7)") (class "Default")
      (node (ref "U$5") (pin "7") (pinfunction "QH_7") (pintype "bidirectional"))
    )
    (net (code "112") (name "unconnected-(U$6-PadP$4)") (class "Default")
      (node (ref "U$6") (pin "P$4") (pinfunction "P$4_P$4") (pintype "bidirectional"))
    )
    (net (code "113") (name "unconnected-(U$6-PadP$8)") (class "Default")
      (node (ref "U$6") (pin "P$8") (pinfunction "P$8_P$8") (pintype "bidirectional"))
    )
    (net (code "114") (name "unconnected-(U$7-PadP$4)") (class "Default")
      (node (ref "U$7") (pin "P$4") (pinfunction "P$4_P$4") (pintype "bidirectional"))
    )
    (net (code "115") (name "unconnected-(U$7-PadP$8)") (class "Default")
      (node (ref "U$7") (pin "P$8") (pinfunction "P$8_P$8") (pintype "bidirectional"))
    )
    (net (code "116") (name "unconnected-(U$8-PadP$4)") (class "Default")
      (node (ref "U$8") (pin "P$4") (pinfunction "P$4_P$4") (pintype "bidirectional"))
    )
    (net (code "117") (name "unconnected-(U$8-PadP$8)") (class "Default")
      (node (ref "U$8") (pin "P$8") (pinfunction "P$8_P$8") (pintype "bidirectional"))
    )
    (net (code "118") (name "unconnected-(U$9-PadP$4)") (class "Default")
      (node (ref "U$9") (pin "P$4") (pinfunction "P$4_P$4") (pintype "bidirectional"))
    )
    (net (code "119") (name "unconnected-(U$9-PadP$8)") (class "Default")
      (node (ref "U$9") (pin "P$8") (pinfunction "P$8_P$8") (pintype "bidirectional"))
    )
    (net (code "120") (name "unconnected-(U$10-PadP$4)") (class "Default")
      (node (ref "U$10") (pin "P$4") (pinfunction "P$4_P$4") (pintype "bidirectional"))
    )
    (net (code "121") (name "unconnected-(U$10-PadP$8)") (class "Default")
      (node (ref "U$10") (pin "P$8") (pinfunction "P$8_P$8") (pintype "bidirectional"))
    )
    (net (code "122") (name "unconnected-(U$11-PadP$4)") (class "Default")
      (node (ref "U$11") (pin "P$4") (pinfunction "P$4_P$4") (pintype "bidirectional"))
    )
    (net (code "123") (name "unconnected-(U$11-PadP$8)") (class "Default")
      (node (ref "U$11") (pin "P$8") (pinfunction "P$8_P$8") (pintype "bidirectional"))
    )
    (net (code "124") (name "unconnected-(U$12-PadP$4)") (class "Default")
      (node (ref "U$12") (pin "P$4") (pinfunction "P$4_P$4") (pintype "bidirectional"))
    )
    (net (code "125") (name "unconnected-(U$12-PadP$8)") (class "Default")
      (node (ref "U$12") (pin "P$8") (pinfunction "P$8_P$8") (pintype "bidirectional"))
    )
    (net (code "126") (name "unconnected-(U$13-PadP$4)") (class "Default")
      (node (ref "U$13") (pin "P$4") (pinfunction "P$4_P$4") (pintype "bidirectional"))
    )
    (net (code "127") (name "unconnected-(U$13-PadP$8)") (class "Default")
      (node (ref "U$13") (pin "P$8") (pinfunction "P$8_P$8") (pintype "bidirectional"))
    )
    (net (code "128") (name "unconnected-(U$14-PadP$4)") (class "Default")
      (node (ref "U$14") (pin "P$4") (pinfunction "P$4_P$4") (pintype "bidirectional"))
    )
    (net (code "129") (name "unconnected-(U$14-PadP$8)") (class "Default")
      (node (ref "U$14") (pin "P$8") (pinfunction "P$8_P$8") (pintype "bidirectional"))
    )
    (net (code "130") (name "unconnected-(U$15-PadP$4)") (class "Default")
      (node (ref "U$15") (pin "P$4") (pinfunction "P$4_P$4") (pintype "bidirectional"))
    )
    (net (code "131") (name "unconnected-(U$15-PadP$8)") (class "Default")
      (node (ref "U$15") (pin "P$8") (pinfunction "P$8_P$8") (pintype "bidirectional"))
    )
  )
)
